# pihat.net
KiCad netlist of a schematic drawn in EAGLE
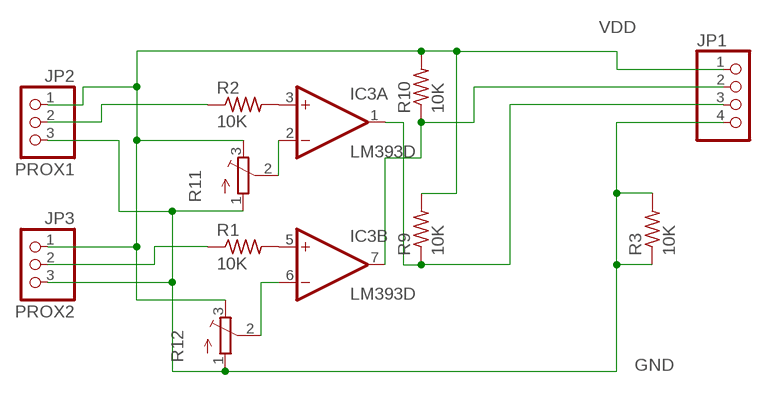
[diagram p0: schematic, sheet 1]

(export (version "E")
  (design (tool "Eeschema 10.0.6"))
  (components
    (comp (ref "IC3")
      (value "LM393D")
      (footprint "eagle-import:SO08")
      (libsource (lib "eagle-import") (part "LM393D"))
    )
    (comp (ref "JP1")
      (value "PINHD-1X4")
      (footprint "eagle-import:1X04")
      (libsource (lib "eagle-import") (part "PINHD-1X4"))
    )
    (comp (ref "JP2")
      (value "PROX1")
      (footprint "eagle-import:1X03")
      (libsource (lib "eagle-import") (part "PINHD-1X3"))
    )
    (comp (ref "JP3")
      (value "PROX2")
      (footprint "eagle-import:1X03")
      (libsource (lib "eagle-import") (part "PINHD-1X3"))
    )
    (comp (ref "R1")
      (value "10K")
      (footprint "eagle-import:R1206FAB")
      (libsource (lib "eagle-import") (part "RES-US1206FAB"))
    )
    (comp (ref "R2")
      (value "10K")
      (footprint "eagle-import:R1206FAB")
      (libsource (lib "eagle-import") (part "RES-US1206FAB"))
    )
    (comp (ref "R3")
      (value "10K")
      (footprint "eagle-import:R1206FAB")
      (libsource (lib "eagle-import") (part "RES-US1206FAB"))
    )
    (comp (ref "R9")
      (value "10K")
      (footprint "eagle-import:R1206FAB")
      (libsource (lib "eagle-import") (part "RES-US1206FAB"))
    )
    (comp (ref "R10")
      (value "10K")
      (footprint "eagle-import:R1206FAB")
      (libsource (lib "eagle-import") (part "RES-US1206FAB"))
    )
    (comp (ref "R11")
      (value "TRIM_EU-3223G")
      (footprint "eagle-import:3223G")
      (libsource (lib "eagle-import") (part "TRIM_EU-3223G"))
    )
    (comp (ref "R12")
      (value "TRIM_EU-3223G")
      (footprint "eagle-import:3223G")
      (libsource (lib "eagle-import") (part "TRIM_EU-3223G"))
    )
  )
  (nets
    (net (code "1") (name "/GND") (class "Default")
      (node (ref "JP1") (pin "4") (pinfunction "4_4") (pintype "passive"))
      (node (ref "JP2") (pin "3") (pinfunction "3_3") (pintype "passive"))
      (node (ref "JP3") (pin "3") (pinfunction "3_3") (pintype "passive"))
      (node (ref "R11") (pin "1") (pinfunction "A_1") (pintype "passive"))
      (node (ref "R12") (pin "1") (pinfunction "A_1") (pintype "passive"))
      (node (ref "R3") (pin "1") (pinfunction "1_1") (pintype "passive"))
      (node (ref "R3") (pin "2") (pinfunction "2_2") (pintype "passive"))
    )
    (net (code "2") (name "/VDD") (class "Default")
      (node (ref "JP1") (pin "1") (pinfunction "1_1") (pintype "passive"))
      (node (ref "JP2") (pin "1") (pinfunction "1_1") (pintype "passive"))
      (node (ref "JP3") (pin "1") (pinfunction "1_1") (pintype "passive"))
      (node (ref "R10") (pin "2") (pinfunction "2_2") (pintype "passive"))
      (node (ref "R11") (pin "3") (pinfunction "E_3") (pintype "passive"))
      (node (ref "R12") (pin "3") (pinfunction "E_3") (pintype "passive"))
      (node (ref "R9") (pin "2") (pinfunction "2_2") (pintype "passive"))
    )
    (net (code "3") (name "Net-(IC3A-+IN)") (class "Default")
      (node (ref "IC3") (pin "3") (pinfunction "+IN_3") (pintype "input"))
      (node (ref "R2") (pin "2") (pinfunction "2_2") (pintype "passive"))
    )
    (net (code "4") (name "Net-(IC3A--IN)") (class "Default")
      (node (ref "IC3") (pin "2") (pinfunction "-IN_2") (pintype "input"))
      (node (ref "R11") (pin "2") (pinfunction "S_2") (pintype "passive"))
    )
    (net (code "5") (name "Net-(IC3A-OUT)") (class "Default")
      (node (ref "IC3") (pin "1") (pinfunction "OUT_1") (pintype "output"))
      (node (ref "JP1") (pin "3") (pinfunction "3_3") (pintype "passive"))
      (node (ref "R9") (pin "1") (pinfunction "1_1") (pintype "passive"))
    )
    (net (code "6") (name "Net-(IC3B-+IN)") (class "Default")
      (node (ref "IC3") (pin "5") (pinfunction "+IN_5") (pintype "input"))
      (node (ref "R1") (pin "2") (pinfunction "2_2") (pintype "passive"))
    )
    (net (code "7") (name "Net-(IC3B--IN)") (class "Default")
      (node (ref "IC3") (pin "6") (pinfunction "-IN_6") (pintype "input"))
      (node (ref "R12") (pin "2") (pinfunction "S_2") (pintype "passive"))
    )
    (net (code "8") (name "Net-(IC3B-OUT)") (class "Default")
      (node (ref "IC3") (pin "7") (pinfunction "OUT_7") (pintype "output"))
      (node (ref "JP1") (pin "2") (pinfunction "2_2") (pintype "passive"))
      (node (ref "R10") (pin "1") (pinfunction "1_1") (pintype "passive"))
    )
    (net (code "9") (name "Net-(JP2-Pad2)") (class "Default")
      (node (ref "JP2") (pin "2") (pinfunction "2_2") (pintype "passive"))
      (node (ref "R2") (pin "1") (pinfunction "1_1") (pintype "passive"))
    )
    (net (code "10") (name "Net-(JP3-Pad2)") (class "Default")
      (node (ref "JP3") (pin "2") (pinfunction "2_2") (pintype "passive"))
      (node (ref "R1") (pin "1") (pinfunction "1_1") (pintype "passive"))
    )
  )
)
